# Connectors.net
KiCad netlist of a schematic drawn in Altium Designer
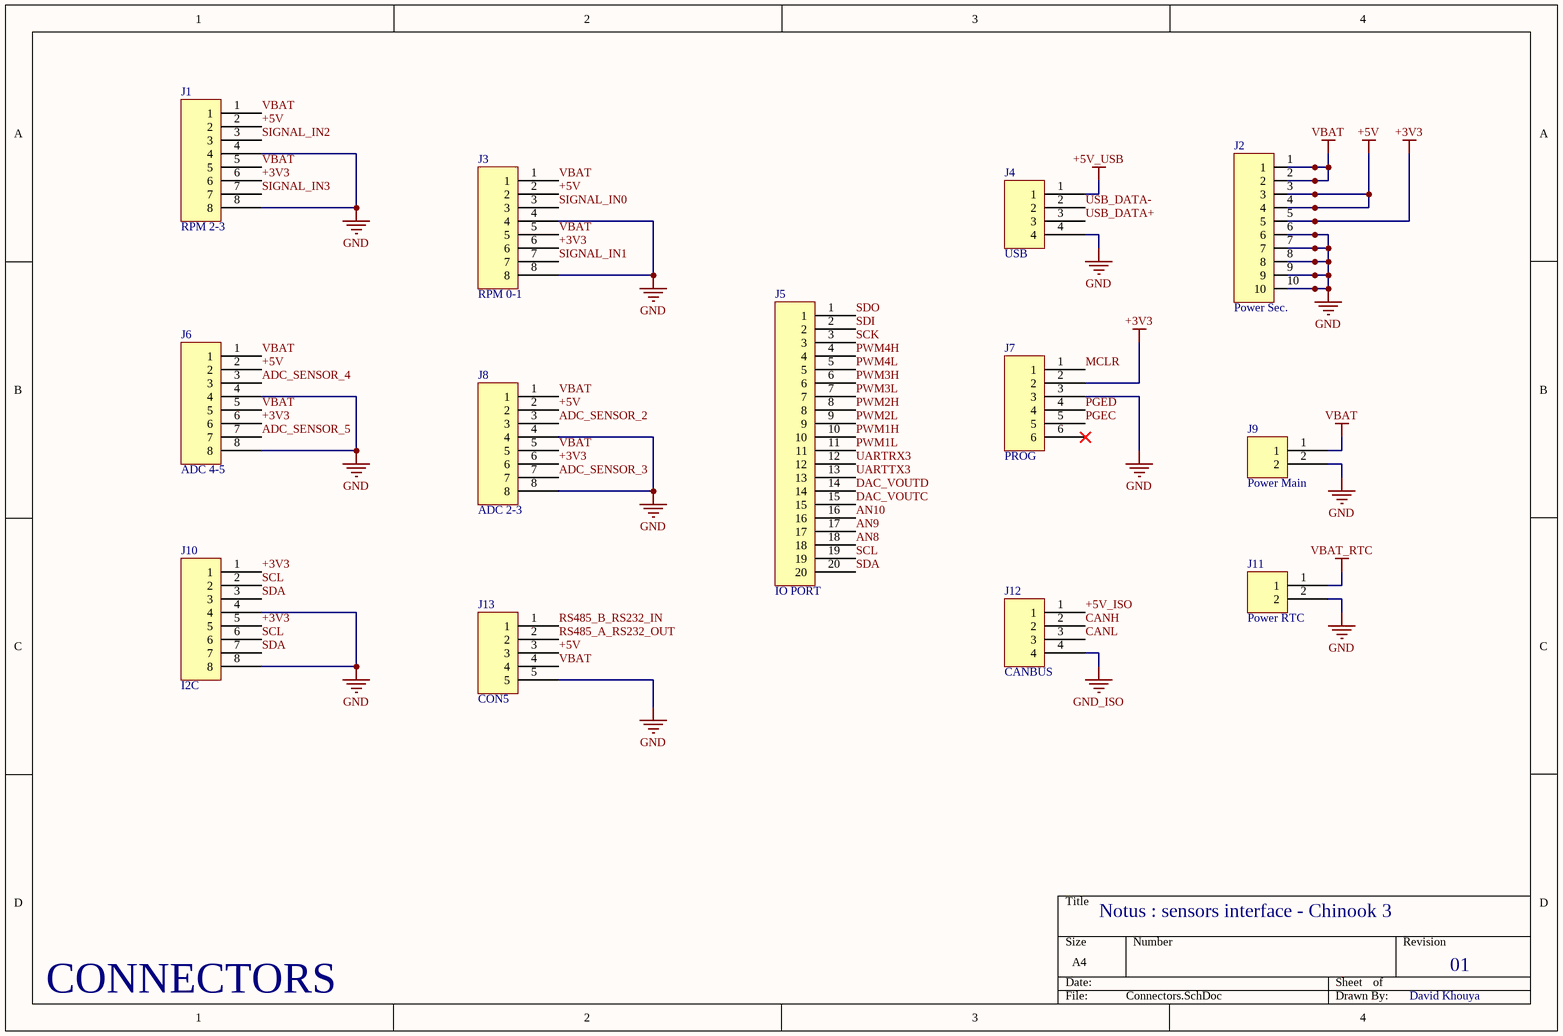
[diagram p0: Connectors.SchDoc]

(export (version "E")
  (design (tool "Eeschema 10.0.6"))
  (components
    (comp (ref "J1")
      (value "RPM 2-3")
      (footprint "1633600000")
      (description "8 pins connector")
      (libsource (lib "dkhouya") (part "CON8"))
    )
    (comp (ref "J2")
      (value "Power Sec.")
      (footprint "104652-1")
      (description "10 pins connector")
      (libsource (lib "dkhouya") (part "CON10"))
    )
    (comp (ref "J3")
      (value "RPM 0-1")
      (footprint "1633600000")
      (description "8 pins connector")
      (libsource (lib "dkhouya") (part "CON8"))
    )
    (comp (ref "J4")
      (value "USB")
      (footprint "AU-Y1007-R")
      (description "4 pins connector")
      (libsource (lib "dkhouya") (part "CON4"))
    )
    (comp (ref "J5")
      (value "IO PORT")
      (footprint "104652-2")
      (description "20 pins connector")
      (libsource (lib "dkhouya") (part "CON20"))
    )
    (comp (ref "J6")
      (value "ADC 4-5")
      (footprint "1633600000")
      (description "8 pins connector")
      (libsource (lib "dkhouya") (part "CON8"))
    )
    (comp (ref "J7")
      (value "PROG")
      (footprint "A31411-ND")
      (description "6 pins connectors")
      (libsource (lib "dkhouya") (part "CON6"))
    )
    (comp (ref "J8")
      (value "ADC 2-3")
      (footprint "1633600000")
      (description "8 pins connector")
      (libsource (lib "dkhouya") (part "CON8"))
    )
    (comp (ref "J9")
      (value "Power Main")
      (footprint "XT60_CON")
      (description "2 pins connector")
      (libsource (lib "dkhouya") (part "CON2"))
    )
    (comp (ref "J10")
      (value "I2C")
      (footprint "1633600000")
      (description "8 pins connector")
      (libsource (lib "dkhouya") (part "CON8"))
    )
    (comp (ref "J11")
      (value "Power RTC")
      (footprint "BS-1225-PC")
      (description "2 pins connector")
      (libsource (lib "dkhouya") (part "CON2"))
    )
    (comp (ref "J12")
      (value "CANBUS")
      (footprint "CON4_100MILS")
      (description "4 pins connector")
      (libsource (lib "dkhouya") (part "CON4"))
    )
    (comp (ref "J13")
      (value "CON5")
      (footprint "1607070000")
      (description "5 pins connector")
      (libsource (lib "dkhouya") (part "CON5"))
    )
  )
  (nets
    (net (code "1") (name "+3V3") (class "Default")
      (node (ref "J1") (pin "6") (pinfunction "6_6") (pintype "passive"))
      (node (ref "J10") (pin "1") (pinfunction "1_1") (pintype "passive"))
      (node (ref "J10") (pin "5") (pinfunction "5_5") (pintype "passive"))
      (node (ref "J2") (pin "5") (pinfunction "5_5") (pintype "passive"))
      (node (ref "J3") (pin "6") (pinfunction "6_6") (pintype "passive"))
      (node (ref "J6") (pin "6") (pinfunction "6_6") (pintype "passive"))
      (node (ref "J7") (pin "2") (pinfunction "2_2") (pintype "passive"))
      (node (ref "J8") (pin "6") (pinfunction "6_6") (pintype "passive"))
    )
    (net (code "2") (name "+5V") (class "Default")
      (node (ref "J1") (pin "2") (pinfunction "2_2") (pintype "passive"))
      (node (ref "J13") (pin "3") (pinfunction "3_3") (pintype "passive"))
      (node (ref "J2") (pin "3") (pinfunction "3_3") (pintype "passive"))
      (node (ref "J2") (pin "4") (pinfunction "4_4") (pintype "passive"))
      (node (ref "J3") (pin "2") (pinfunction "2_2") (pintype "passive"))
      (node (ref "J6") (pin "2") (pinfunction "2_2") (pintype "passive"))
      (node (ref "J8") (pin "2") (pinfunction "2_2") (pintype "passive"))
    )
    (net (code "3") (name "+5V_USB") (class "Default")
      (node (ref "J4") (pin "1") (pinfunction "1_1") (pintype "passive"))
    )
    (net (code "4") (name "/+5V_ISO") (class "Default")
      (node (ref "J12") (pin "1") (pinfunction "1_1") (pintype "passive"))
    )
    (net (code "5") (name "/ADC_SENSOR_2") (class "Default")
      (node (ref "J8") (pin "3") (pinfunction "3_3") (pintype "passive"))
    )
    (net (code "6") (name "/ADC_SENSOR_3") (class "Default")
      (node (ref "J8") (pin "7") (pinfunction "7_7") (pintype "passive"))
    )
    (net (code "7") (name "/ADC_SENSOR_4") (class "Default")
      (node (ref "J6") (pin "3") (pinfunction "3_3") (pintype "passive"))
    )
    (net (code "8") (name "/ADC_SENSOR_5") (class "Default")
      (node (ref "J6") (pin "7") (pinfunction "7_7") (pintype "passive"))
    )
    (net (code "9") (name "/AN8") (class "Default")
      (node (ref "J5") (pin "18") (pinfunction "18_18") (pintype "passive"))
    )
    (net (code "10") (name "/AN9") (class "Default")
      (node (ref "J5") (pin "17") (pinfunction "17_17") (pintype "passive"))
    )
    (net (code "11") (name "/AN10") (class "Default")
      (node (ref "J5") (pin "16") (pinfunction "16_16") (pintype "passive"))
    )
    (net (code "12") (name "/CANH") (class "Default")
      (node (ref "J12") (pin "2") (pinfunction "2_2") (pintype "passive"))
    )
    (net (code "13") (name "/CANL") (class "Default")
      (node (ref "J12") (pin "3") (pinfunction "3_3") (pintype "passive"))
    )
    (net (code "14") (name "/DAC_VOUTC") (class "Default")
      (node (ref "J5") (pin "15") (pinfunction "15_15") (pintype "passive"))
    )
    (net (code "15") (name "/DAC_VOUTD") (class "Default")
      (node (ref "J5") (pin "14") (pinfunction "14_14") (pintype "passive"))
    )
    (net (code "16") (name "/MCLR") (class "Default")
      (node (ref "J7") (pin "1") (pinfunction "1_1") (pintype "passive"))
    )
    (net (code "17") (name "/PGEC") (class "Default")
      (node (ref "J7") (pin "5") (pinfunction "5_5") (pintype "passive"))
    )
    (net (code "18") (name "/PGED") (class "Default")
      (node (ref "J7") (pin "4") (pinfunction "4_4") (pintype "passive"))
    )
    (net (code "19") (name "/PWM1H") (class "Default")
      (node (ref "J5") (pin "10") (pinfunction "10_10") (pintype "passive"))
    )
    (net (code "20") (name "/PWM1L") (class "Default")
      (node (ref "J5") (pin "11") (pinfunction "11_11") (pintype "passive"))
    )
    (net (code "21") (name "/PWM2H") (class "Default")
      (node (ref "J5") (pin "8") (pinfunction "8_8") (pintype "passive"))
    )
    (net (code "22") (name "/PWM2L") (class "Default")
      (node (ref "J5") (pin "9") (pinfunction "9_9") (pintype "passive"))
    )
    (net (code "23") (name "/PWM3H") (class "Default")
      (node (ref "J5") (pin "6") (pinfunction "6_6") (pintype "passive"))
    )
    (net (code "24") (name "/PWM3L") (class "Default")
      (node (ref "J5") (pin "7") (pinfunction "7_7") (pintype "passive"))
    )
    (net (code "25") (name "/PWM4H") (class "Default")
      (node (ref "J5") (pin "4") (pinfunction "4_4") (pintype "passive"))
    )
    (net (code "26") (name "/PWM4L") (class "Default")
      (node (ref "J5") (pin "5") (pinfunction "5_5") (pintype "passive"))
    )
    (net (code "27") (name "/RS485_A_RS232_OUT") (class "Default")
      (node (ref "J13") (pin "2") (pinfunction "2_2") (pintype "passive"))
    )
    (net (code "28") (name "/RS485_B_RS232_IN") (class "Default")
      (node (ref "J13") (pin "1") (pinfunction "1_1") (pintype "passive"))
    )
    (net (code "29") (name "/SCK") (class "Default")
      (node (ref "J5") (pin "3") (pinfunction "3_3") (pintype "passive"))
    )
    (net (code "30") (name "/SCL") (class "Default")
      (node (ref "J10") (pin "2") (pinfunction "2_2") (pintype "passive"))
      (node (ref "J10") (pin "6") (pinfunction "6_6") (pintype "passive"))
      (node (ref "J5") (pin "19") (pinfunction "19_19") (pintype "passive"))
    )
    (net (code "31") (name "/SDA") (class "Default")
      (node (ref "J10") (pin "3") (pinfunction "3_3") (pintype "passive"))
      (node (ref "J10") (pin "7") (pinfunction "7_7") (pintype "passive"))
      (node (ref "J5") (pin "20") (pinfunction "20_20") (pintype "passive"))
    )
    (net (code "32") (name "/SDI") (class "Default")
      (node (ref "J5") (pin "2") (pinfunction "2_2") (pintype "passive"))
    )
    (net (code "33") (name "/SDO") (class "Default")
      (node (ref "J5") (pin "1") (pinfunction "1_1") (pintype "passive"))
    )
    (net (code "34") (name "/SIGNAL_IN0") (class "Default")
      (node (ref "J3") (pin "3") (pinfunction "3_3") (pintype "passive"))
    )
    (net (code "35") (name "/SIGNAL_IN1") (class "Default")
      (node (ref "J3") (pin "7") (pinfunction "7_7") (pintype "passive"))
    )
    (net (code "36") (name "/SIGNAL_IN2") (class "Default")
      (node (ref "J1") (pin "3") (pinfunction "3_3") (pintype "passive"))
    )
    (net (code "37") (name "/SIGNAL_IN3") (class "Default")
      (node (ref "J1") (pin "7") (pinfunction "7_7") (pintype "passive"))
    )
    (net (code "38") (name "/UARTRX3") (class "Default")
      (node (ref "J5") (pin "12") (pinfunction "12_12") (pintype "passive"))
    )
    (net (code "39") (name "/UARTTX3") (class "Default")
      (node (ref "J5") (pin "13") (pinfunction "13_13") (pintype "passive"))
    )
    (net (code "40") (name "/USB_DATA+") (class "Default")
      (node (ref "J4") (pin "3") (pinfunction "3_3") (pintype "passive"))
    )
    (net (code "41") (name "/USB_DATA-") (class "Default")
      (node (ref "J4") (pin "2") (pinfunction "2_2") (pintype "passive"))
    )
    (net (code "42") (name "GND") (class "Default")
      (node (ref "J1") (pin "4") (pinfunction "4_4") (pintype "passive"))
      (node (ref "J1") (pin "8") (pinfunction "8_8") (pintype "passive"))
      (node (ref "J10") (pin "4") (pinfunction "4_4") (pintype "passive"))
      (node (ref "J10") (pin "8") (pinfunction "8_8") (pintype "passive"))
      (node (ref "J11") (pin "2") (pinfunction "2_2") (pintype "passive"))
      (node (ref "J13") (pin "5") (pinfunction "5_5") (pintype "passive"))
      (node (ref "J2") (pin "10") (pinfunction "10_10") (pintype "passive"))
      (node (ref "J2") (pin "6") (pinfunction "6_6") (pintype "passive"))
      (node (ref "J2") (pin "7") (pinfunction "7_7") (pintype "passive"))
      (node (ref "J2") (pin "8") (pinfunction "8_8") (pintype "passive"))
      (node (ref "J2") (pin "9") (pinfunction "9_9") (pintype "passive"))
      (node (ref "J3") (pin "4") (pinfunction "4_4") (pintype "passive"))
      (node (ref "J3") (pin "8") (pinfunction "8_8") (pintype "passive"))
      (node (ref "J4") (pin "4") (pinfunction "4_4") (pintype "passive"))
      (node (ref "J6") (pin "4") (pinfunction "4_4") (pintype "passive"))
      (node (ref "J6") (pin "8") (pinfunction "8_8") (pintype "passive"))
      (node (ref "J7") (pin "3") (pinfunction "3_3") (pintype "passive"))
      (node (ref "J8") (pin "4") (pinfunction "4_4") (pintype "passive"))
      (node (ref "J8") (pin "8") (pinfunction "8_8") (pintype "passive"))
      (node (ref "J9") (pin "2") (pinfunction "2_2") (pintype "passive"))
    )
    (net (code "43") (name "GND_ISO") (class "Default")
      (node (ref "J12") (pin "4") (pinfunction "4_4") (pintype "passive"))
    )
    (net (code "44") (name "VBAT") (class "Default")
      (node (ref "J1") (pin "1") (pinfunction "1_1") (pintype "passive"))
      (node (ref "J1") (pin "5") (pinfunction "5_5") (pintype "passive"))
      (node (ref "J13") (pin "4") (pinfunction "4_4") (pintype "passive"))
      (node (ref "J2") (pin "1") (pinfunction "1_1") (pintype "passive"))
      (node (ref "J2") (pin "2") (pinfunction "2_2") (pintype "passive"))
      (node (ref "J3") (pin "1") (pinfunction "1_1") (pintype "passive"))
      (node (ref "J3") (pin "5") (pinfunction "5_5") (pintype "passive"))
      (node (ref "J6") (pin "1") (pinfunction "1_1") (pintype "passive"))
      (node (ref "J6") (pin "5") (pinfunction "5_5") (pintype "passive"))
      (node (ref "J8") (pin "1") (pinfunction "1_1") (pintype "passive"))
      (node (ref "J8") (pin "5") (pinfunction "5_5") (pintype "passive"))
      (node (ref "J9") (pin "1") (pinfunction "1_1") (pintype "passive"))
    )
    (net (code "45") (name "VBAT_RTC") (class "Default")
      (node (ref "J11") (pin "1") (pinfunction "1_1") (pintype "passive"))
    )
    (net (code "46") (name "unconnected-(J7-Pad6)") (class "Default")
      (node (ref "J7") (pin "6") (pinfunction "6_6") (pintype "passive+no_connect"))
    )
  )
)
